# TAG.net
KiCad netlist of a schematic drawn in Altium Designer
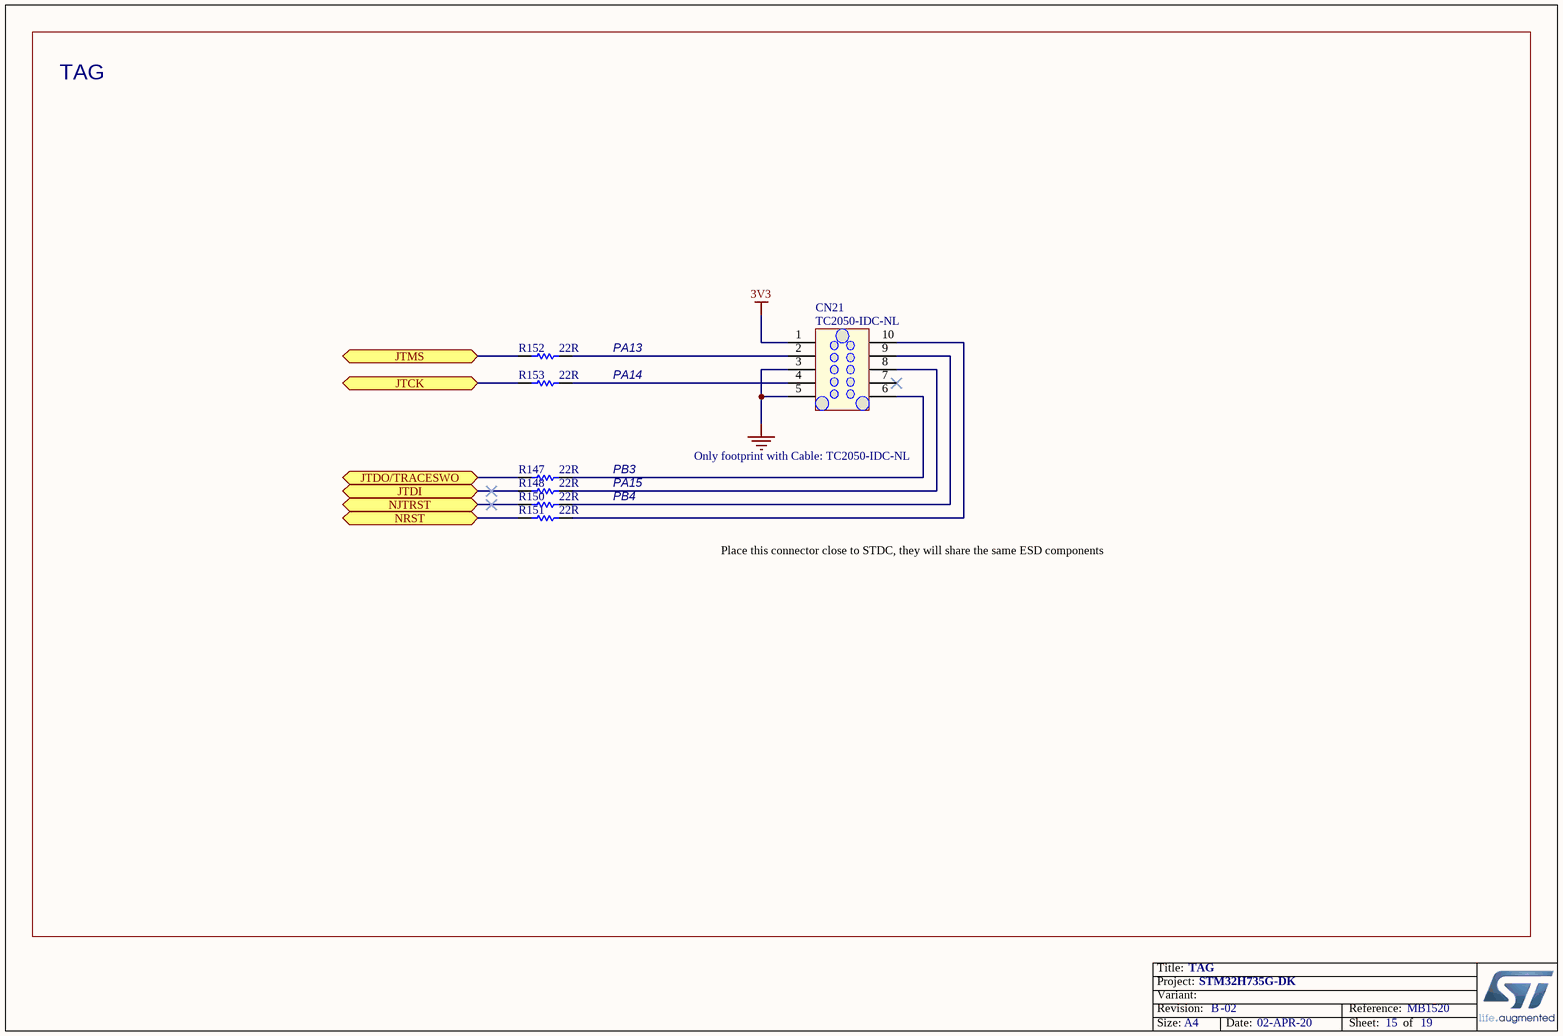
[diagram p0: TAG.SchDoc]

(export (version "E")
  (design (tool "Eeschema 10.0.6"))
  (components
    (comp (ref "CN21")
      (value "TC2050-IDC-NL")
      (footprint "CON_TAG-C_TC2050-IDC-NL")
      (description "Tag_Connector Header, 10x2, No legs")
      (fields
        (field (name "INTERNAL_PART_NUMBER") "MCD-00031")
        (field (name "MANUFACTURER_PART_NUMBER") "TC2050-IDC-NL-FP")
        (field (name "PROVIDED_BY") "SUBCO")
      )
      (libsource (lib "MCD_PARTS_database") (part "Tag-10-C"))
    )
    (comp (ref "R147")
      (value "22R")
      (footprint "R0402")
      (description "Resistor,22R,0402,1%,1/16W")
      (fields
        (field (name "INTERNAL_PART_NUMBER") "MCD-00189")
        (field (name "MANUFACTURER_PART_NUMBER") "RC0402FR-0722RL")
        (field (name "PROVIDED_BY") "SUBCO")
      )
      (libsource (lib "MCD_PARTS_database") (part "Resistor"))
    )
    (comp (ref "R148")
      (value "22R")
      (footprint "R0402")
      (description "Resistor,22R,0402,1%,1/16W")
      (fields
        (field (name "INTERNAL_PART_NUMBER") "MCD-00189")
        (field (name "MANUFACTURER_PART_NUMBER") "RC0402FR-0722RL")
        (field (name "PROVIDED_BY") "SUBCO")
      )
      (libsource (lib "MCD_PARTS_database") (part "Resistor"))
    )
    (comp (ref "R150")
      (value "22R")
      (footprint "R0402")
      (description "Resistor,22R,0402,1%,1/16W")
      (fields
        (field (name "INTERNAL_PART_NUMBER") "MCD-00189")
        (field (name "MANUFACTURER_PART_NUMBER") "RC0402FR-0722RL")
        (field (name "PROVIDED_BY") "SUBCO")
      )
      (libsource (lib "MCD_PARTS_database") (part "Resistor"))
    )
    (comp (ref "R151")
      (value "22R")
      (footprint "R0402")
      (description "Resistor,22R,0402,1%,1/16W")
      (fields
        (field (name "INTERNAL_PART_NUMBER") "MCD-00189")
        (field (name "MANUFACTURER_PART_NUMBER") "RC0402FR-0722RL")
        (field (name "PROVIDED_BY") "SUBCO")
      )
      (libsource (lib "MCD_PARTS_database") (part "Resistor"))
    )
    (comp (ref "R152")
      (value "22R")
      (footprint "R0402")
      (description "Resistor,22R,0402,1%,1/16W")
      (fields
        (field (name "INTERNAL_PART_NUMBER") "MCD-00189")
        (field (name "MANUFACTURER_PART_NUMBER") "RC0402FR-0722RL")
        (field (name "PROVIDED_BY") "SUBCO")
      )
      (libsource (lib "MCD_PARTS_database") (part "Resistor"))
    )
    (comp (ref "R153")
      (value "22R")
      (footprint "R0402")
      (description "Resistor,22R,0402,1%,1/16W")
      (fields
        (field (name "INTERNAL_PART_NUMBER") "MCD-00189")
        (field (name "MANUFACTURER_PART_NUMBER") "RC0402FR-0722RL")
        (field (name "PROVIDED_BY") "SUBCO")
      )
      (libsource (lib "MCD_PARTS_database") (part "Resistor"))
    )
  )
  (nets
    (net (code "1") (name "/JTCK") (class "Default")
      (node (ref "R153") (pin "1") (pinfunction "1_1") (pintype "passive"))
    )
    (net (code "2") (name "/JTDI") (class "Default")
      (node (ref "R148") (pin "1") (pinfunction "1_1") (pintype "passive"))
    )
    (net (code "3") (name "/JTDO{slash}TRACESWO") (class "Default")
      (node (ref "R147") (pin "1") (pinfunction "1_1") (pintype "passive"))
    )
    (net (code "4") (name "/JTMS") (class "Default")
      (node (ref "R152") (pin "1") (pinfunction "1_1") (pintype "passive"))
    )
    (net (code "5") (name "/NJTRST") (class "Default")
      (node (ref "R150") (pin "1") (pinfunction "1_1") (pintype "passive"))
    )
    (net (code "6") (name "/NRST") (class "Default")
      (node (ref "R151") (pin "1") (pinfunction "1_1") (pintype "passive"))
    )
    (net (code "7") (name "3V3") (class "Default")
      (node (ref "CN21") (pin "1") (pinfunction "1_1") (pintype "passive"))
    )
    (net (code "8") (name "GND") (class "Default")
      (node (ref "CN21") (pin "3") (pinfunction "3_3") (pintype "passive"))
      (node (ref "CN21") (pin "5") (pinfunction "5_5") (pintype "passive"))
    )
    (net (code "9") (name "Net-(CN21-Pad2)") (class "Default")
      (node (ref "CN21") (pin "2") (pinfunction "2_2") (pintype "passive"))
      (node (ref "R152") (pin "2") (pinfunction "2_2") (pintype "passive"))
    )
    (net (code "10") (name "Net-(CN21-Pad4)") (class "Default")
      (node (ref "CN21") (pin "4") (pinfunction "4_4") (pintype "passive"))
      (node (ref "R153") (pin "2") (pinfunction "2_2") (pintype "passive"))
    )
    (net (code "11") (name "Net-(CN21-Pad6)") (class "Default")
      (node (ref "CN21") (pin "6") (pinfunction "6_6") (pintype "passive"))
      (node (ref "R147") (pin "2") (pinfunction "2_2") (pintype "passive"))
    )
    (net (code "12") (name "Net-(CN21-Pad8)") (class "Default")
      (node (ref "CN21") (pin "8") (pinfunction "8_8") (pintype "passive"))
      (node (ref "R148") (pin "2") (pinfunction "2_2") (pintype "passive"))
    )
    (net (code "13") (name "Net-(CN21-Pad9)") (class "Default")
      (node (ref "CN21") (pin "9") (pinfunction "9_9") (pintype "passive"))
      (node (ref "R150") (pin "2") (pinfunction "2_2") (pintype "passive"))
    )
    (net (code "14") (name "Net-(CN21-Pad10)") (class "Default")
      (node (ref "CN21") (pin "10") (pinfunction "10_10") (pintype "passive"))
      (node (ref "R151") (pin "2") (pinfunction "2_2") (pintype "passive"))
    )
    (net (code "15") (name "unconnected-(CN21-Pad7)") (class "Default")
      (node (ref "CN21") (pin "7") (pinfunction "7_7") (pintype "passive+no_connect"))
    )
  )
)
